# FPGA_bank15_16.net
KiCad netlist of a schematic drawn in Altium Designer
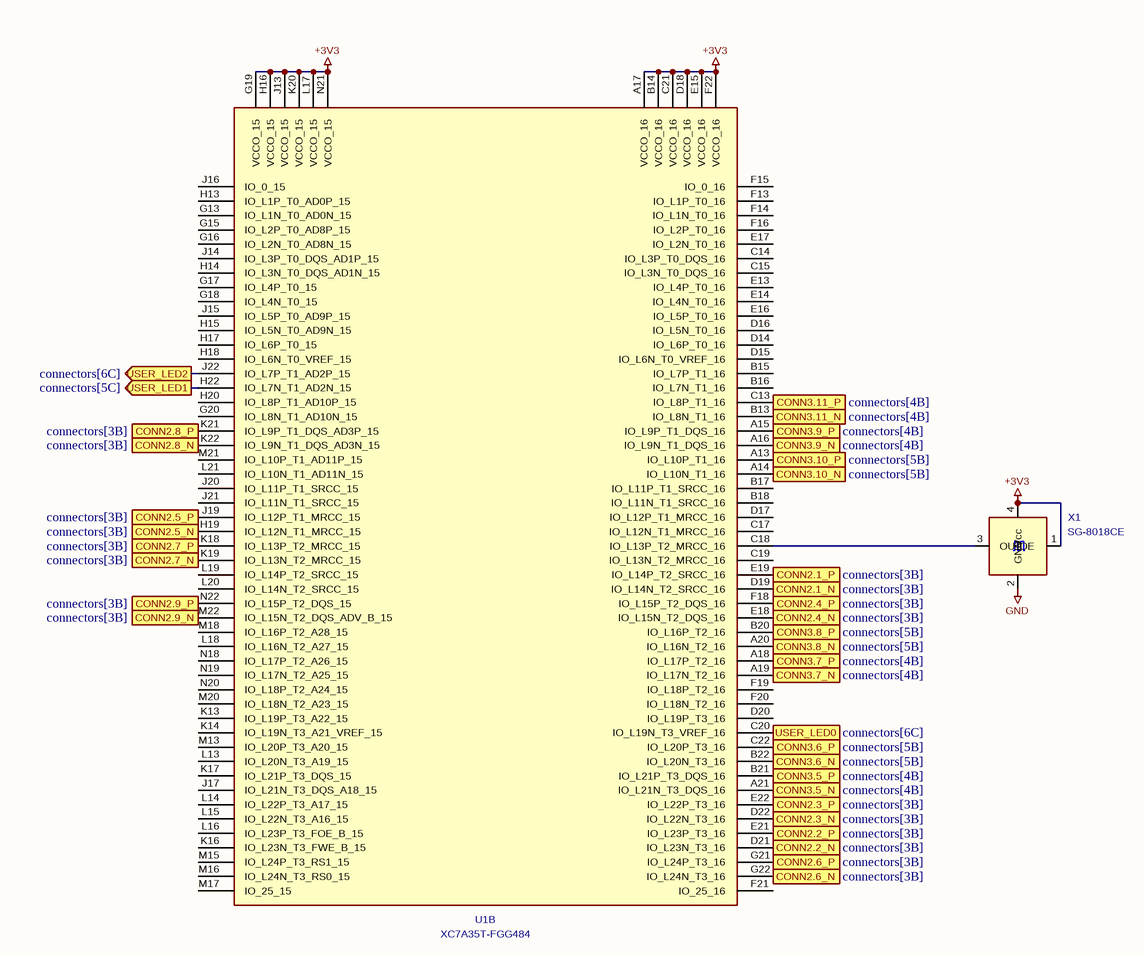
[diagram p0: FPGA_bank15_16.SchDoc]

(export (version "E")
  (design (tool "Eeschema 10.0.6"))
  (components
    (comp (ref "U1")
      (value "XC7A35T-FGG484")
      (footprint "FB-BGA-484_23.0x23.0mm_Layout22x22_P1.0mm")
      (libsource (lib "som_fpga") (part "XC7A35T-FGG484"))
    )
    (comp (ref "X1")
      (value "SG-8018CE")
      (footprint "Crystal_SMD_3225-4Pin_3.2x2.5mm")
      (libsource (lib "Oscillator") (part "SG-5032CCN"))
    )
  )
  (nets
    (net (code "1") (name "+3V3") (class "Default")
      (node (ref "U1") (pin "A17") (pinfunction "VCCO_16_A17") (pintype "passive"))
      (node (ref "U1") (pin "B14") (pinfunction "VCCO_16_B14") (pintype "passive"))
      (node (ref "U1") (pin "C21") (pinfunction "VCCO_16_C21") (pintype "passive"))
      (node (ref "U1") (pin "D18") (pinfunction "VCCO_16_D18") (pintype "passive"))
      (node (ref "U1") (pin "E15") (pinfunction "VCCO_16_E15") (pintype "passive"))
      (node (ref "U1") (pin "F22") (pinfunction "VCCO_16_F22") (pintype "passive"))
      (node (ref "U1") (pin "G19") (pinfunction "VCCO_15_G19") (pintype "passive"))
      (node (ref "U1") (pin "H16") (pinfunction "VCCO_15_H16") (pintype "passive"))
      (node (ref "U1") (pin "J13") (pinfunction "VCCO_15_J13") (pintype "passive"))
      (node (ref "U1") (pin "K20") (pinfunction "VCCO_15_K20") (pintype "passive"))
      (node (ref "U1") (pin "L17") (pinfunction "VCCO_15_L17") (pintype "passive"))
      (node (ref "U1") (pin "N21") (pinfunction "VCCO_15_N21") (pintype "passive"))
      (node (ref "X1") (pin "1") (pinfunction "OE_1") (pintype "passive"))
      (node (ref "X1") (pin "4") (pinfunction "Vcc_4") (pintype "passive"))
    )
    (net (code "2") (name "/CONN2.1_N") (class "Default")
      (node (ref "U1") (pin "D19") (pinfunction "IO_L14N_T2_SRCC_16_D19") (pintype "passive"))
    )
    (net (code "3") (name "/CONN2.1_P") (class "Default")
      (node (ref "U1") (pin "E19") (pinfunction "IO_L14P_T2_SRCC_16_E19") (pintype "passive"))
    )
    (net (code "4") (name "/CONN2.2_N") (class "Default")
      (node (ref "U1") (pin "D21") (pinfunction "IO_L23N_T3_16_D21") (pintype "passive"))
    )
    (net (code "5") (name "/CONN2.2_P") (class "Default")
      (node (ref "U1") (pin "E21") (pinfunction "IO_L23P_T3_16_E21") (pintype "passive"))
    )
    (net (code "6") (name "/CONN2.3_N") (class "Default")
      (node (ref "U1") (pin "D22") (pinfunction "IO_L22N_T3_16_D22") (pintype "passive"))
    )
    (net (code "7") (name "/CONN2.3_P") (class "Default")
      (node (ref "U1") (pin "E22") (pinfunction "IO_L22P_T3_16_E22") (pintype "passive"))
    )
    (net (code "8") (name "/CONN2.4_N") (class "Default")
      (node (ref "U1") (pin "E18") (pinfunction "IO_L15N_T2_DQS_16_E18") (pintype "passive"))
    )
    (net (code "9") (name "/CONN2.4_P") (class "Default")
      (node (ref "U1") (pin "F18") (pinfunction "IO_L15P_T2_DQS_16_F18") (pintype "passive"))
    )
    (net (code "10") (name "/CONN2.5_N") (class "Default")
      (node (ref "U1") (pin "H19") (pinfunction "IO_L12N_T1_MRCC_15_H19") (pintype "passive"))
    )
    (net (code "11") (name "/CONN2.5_P") (class "Default")
      (node (ref "U1") (pin "J19") (pinfunction "IO_L12P_T1_MRCC_15_J19") (pintype "passive"))
    )
    (net (code "12") (name "/CONN2.6_N") (class "Default")
      (node (ref "U1") (pin "G22") (pinfunction "IO_L24N_T3_16_G22") (pintype "passive"))
    )
    (net (code "13") (name "/CONN2.6_P") (class "Default")
      (node (ref "U1") (pin "G21") (pinfunction "IO_L24P_T3_16_G21") (pintype "passive"))
    )
    (net (code "14") (name "/CONN2.7_N") (class "Default")
      (node (ref "U1") (pin "K19") (pinfunction "IO_L13N_T2_MRCC_15_K19") (pintype "passive"))
    )
    (net (code "15") (name "/CONN2.7_P") (class "Default")
      (node (ref "U1") (pin "K18") (pinfunction "IO_L13P_T2_MRCC_15_K18") (pintype "passive"))
    )
    (net (code "16") (name "/CONN2.8_N") (class "Default")
      (node (ref "U1") (pin "K22") (pinfunction "IO_L9N_T1_DQS_AD3N_15_K22") (pintype "passive"))
    )
    (net (code "17") (name "/CONN2.8_P") (class "Default")
      (node (ref "U1") (pin "K21") (pinfunction "IO_L9P_T1_DQS_AD3P_15_K21") (pintype "passive"))
    )
    (net (code "18") (name "/CONN2.9_N") (class "Default")
      (node (ref "U1") (pin "M22") (pinfunction "IO_L15N_T2_DQS_ADV_B_15_M22") (pintype "passive"))
    )
    (net (code "19") (name "/CONN2.9_P") (class "Default")
      (node (ref "U1") (pin "N22") (pinfunction "IO_L15P_T2_DQS_15_N22") (pintype "passive"))
    )
    (net (code "20") (name "/CONN3.5_N") (class "Default")
      (node (ref "U1") (pin "A21") (pinfunction "IO_L21N_T3_DQS_16_A21") (pintype "passive"))
    )
    (net (code "21") (name "/CONN3.5_P") (class "Default")
      (node (ref "U1") (pin "B21") (pinfunction "IO_L21P_T3_DQS_16_B21") (pintype "passive"))
    )
    (net (code "22") (name "/CONN3.6_N") (class "Default")
      (node (ref "U1") (pin "B22") (pinfunction "IO_L20N_T3_16_B22") (pintype "passive"))
    )
    (net (code "23") (name "/CONN3.6_P") (class "Default")
      (node (ref "U1") (pin "C22") (pinfunction "IO_L20P_T3_16_C22") (pintype "passive"))
    )
    (net (code "24") (name "/CONN3.7_N") (class "Default")
      (node (ref "U1") (pin "A19") (pinfunction "IO_L17N_T2_16_A19") (pintype "passive"))
    )
    (net (code "25") (name "/CONN3.7_P") (class "Default")
      (node (ref "U1") (pin "A18") (pinfunction "IO_L17P_T2_16_A18") (pintype "passive"))
    )
    (net (code "26") (name "/CONN3.8_N") (class "Default")
      (node (ref "U1") (pin "A20") (pinfunction "IO_L16N_T2_16_A20") (pintype "passive"))
    )
    (net (code "27") (name "/CONN3.8_P") (class "Default")
      (node (ref "U1") (pin "B20") (pinfunction "IO_L16P_T2_16_B20") (pintype "passive"))
    )
    (net (code "28") (name "/CONN3.9_N") (class "Default")
      (node (ref "U1") (pin "A16") (pinfunction "IO_L9N_T1_DQS_16_A16") (pintype "passive"))
    )
    (net (code "29") (name "/CONN3.9_P") (class "Default")
      (node (ref "U1") (pin "A15") (pinfunction "IO_L9P_T1_DQS_16_A15") (pintype "passive"))
    )
    (net (code "30") (name "/CONN3.10_N") (class "Default")
      (node (ref "U1") (pin "A14") (pinfunction "IO_L10N_T1_16_A14") (pintype "passive"))
    )
    (net (code "31") (name "/CONN3.10_P") (class "Default")
      (node (ref "U1") (pin "A13") (pinfunction "IO_L10P_T1_16_A13") (pintype "passive"))
    )
    (net (code "32") (name "/CONN3.11_N") (class "Default")
      (node (ref "U1") (pin "B13") (pinfunction "IO_L8N_T1_16_B13") (pintype "passive"))
    )
    (net (code "33") (name "/CONN3.11_P") (class "Default")
      (node (ref "U1") (pin "C13") (pinfunction "IO_L8P_T1_16_C13") (pintype "passive"))
    )
    (net (code "34") (name "/USER_LED0") (class "Default")
      (node (ref "U1") (pin "C20") (pinfunction "IO_L19N_T3_VREF_16_C20") (pintype "passive"))
    )
    (net (code "35") (name "/USER_LED1") (class "Default")
      (node (ref "U1") (pin "H22") (pinfunction "IO_L7N_T1_AD2N_15_H22") (pintype "passive"))
    )
    (net (code "36") (name "/USER_LED2") (class "Default")
      (node (ref "U1") (pin "J22") (pinfunction "IO_L7P_T1_AD2P_15_J22") (pintype "passive"))
    )
    (net (code "37") (name "GND") (class "Default")
      (node (ref "X1") (pin "2") (pinfunction "GND_2") (pintype "passive"))
    )
    (net (code "38") (name "Net-(U1B-IO_L13P_T2_MRCC_16)") (class "Default")
      (node (ref "U1") (pin "C18") (pinfunction "IO_L13P_T2_MRCC_16_C18") (pintype "passive"))
      (node (ref "X1") (pin "3") (pinfunction "OUT_3") (pintype "passive"))
    )
    (net (code "39") (name "unconnected-(U1B-IO_0_15-PadJ16)") (class "Default")
      (node (ref "U1") (pin "J16") (pinfunction "IO_0_15_J16") (pintype "passive"))
    )
    (net (code "40") (name "unconnected-(U1B-IO_0_16-PadF15)") (class "Default")
      (node (ref "U1") (pin "F15") (pinfunction "IO_0_16_F15") (pintype "passive"))
    )
    (net (code "41") (name "unconnected-(U1B-IO_25_15-PadM17)") (class "Default")
      (node (ref "U1") (pin "M17") (pinfunction "IO_25_15_M17") (pintype "passive"))
    )
    (net (code "42") (name "unconnected-(U1B-IO_25_16-PadF21)") (class "Default")
      (node (ref "U1") (pin "F21") (pinfunction "IO_25_16_F21") (pintype "passive"))
    )
    (net (code "43") (name "unconnected-(U1B-IO_L1N_T0_16-PadF14)") (class "Default")
      (node (ref "U1") (pin "F14") (pinfunction "IO_L1N_T0_16_F14") (pintype "passive"))
    )
    (net (code "44") (name "unconnected-(U1B-IO_L1N_T0_AD0N_15-PadG13)") (class "Default")
      (node (ref "U1") (pin "G13") (pinfunction "IO_L1N_T0_AD0N_15_G13") (pintype "passive"))
    )
    (net (code "45") (name "unconnected-(U1B-IO_L1P_T0_16-PadF13)") (class "Default")
      (node (ref "U1") (pin "F13") (pinfunction "IO_L1P_T0_16_F13") (pintype "passive"))
    )
    (net (code "46") (name "unconnected-(U1B-IO_L1P_T0_AD0P_15-PadH13)") (class "Default")
      (node (ref "U1") (pin "H13") (pinfunction "IO_L1P_T0_AD0P_15_H13") (pintype "passive"))
    )
    (net (code "47") (name "unconnected-(U1B-IO_L2N_T0_16-PadE17)") (class "Default")
      (node (ref "U1") (pin "E17") (pinfunction "IO_L2N_T0_16_E17") (pintype "passive"))
    )
    (net (code "48") (name "unconnected-(U1B-IO_L2N_T0_AD8N_15-PadG16)") (class "Default")
      (node (ref "U1") (pin "G16") (pinfunction "IO_L2N_T0_AD8N_15_G16") (pintype "passive"))
    )
    (net (code "49") (name "unconnected-(U1B-IO_L2P_T0_16-PadF16)") (class "Default")
      (node (ref "U1") (pin "F16") (pinfunction "IO_L2P_T0_16_F16") (pintype "passive"))
    )
    (net (code "50") (name "unconnected-(U1B-IO_L2P_T0_AD8P_15-PadG15)") (class "Default")
      (node (ref "U1") (pin "G15") (pinfunction "IO_L2P_T0_AD8P_15_G15") (pintype "passive"))
    )
    (net (code "51") (name "unconnected-(U1B-IO_L3N_T0_DQS_16-PadC15)") (class "Default")
      (node (ref "U1") (pin "C15") (pinfunction "IO_L3N_T0_DQS_16_C15") (pintype "passive"))
    )
    (net (code "52") (name "unconnected-(U1B-IO_L3N_T0_DQS_AD1N_15-PadH14)") (class "Default")
      (node (ref "U1") (pin "H14") (pinfunction "IO_L3N_T0_DQS_AD1N_15_H14") (pintype "passive"))
    )
    (net (code "53") (name "unconnected-(U1B-IO_L3P_T0_DQS_16-PadC14)") (class "Default")
      (node (ref "U1") (pin "C14") (pinfunction "IO_L3P_T0_DQS_16_C14") (pintype "passive"))
    )
    (net (code "54") (name "unconnected-(U1B-IO_L3P_T0_DQS_AD1P_15-PadJ14)") (class "Default")
      (node (ref "U1") (pin "J14") (pinfunction "IO_L3P_T0_DQS_AD1P_15_J14") (pintype "passive"))
    )
    (net (code "55") (name "unconnected-(U1B-IO_L4N_T0_15-PadG18)") (class "Default")
      (node (ref "U1") (pin "G18") (pinfunction "IO_L4N_T0_15_G18") (pintype "passive"))
    )
    (net (code "56") (name "unconnected-(U1B-IO_L4N_T0_16-PadE14)") (class "Default")
      (node (ref "U1") (pin "E14") (pinfunction "IO_L4N_T0_16_E14") (pintype "passive"))
    )
    (net (code "57") (name "unconnected-(U1B-IO_L4P_T0_15-PadG17)") (class "Default")
      (node (ref "U1") (pin "G17") (pinfunction "IO_L4P_T0_15_G17") (pintype "passive"))
    )
    (net (code "58") (name "unconnected-(U1B-IO_L4P_T0_16-PadE13)") (class "Default")
      (node (ref "U1") (pin "E13") (pinfunction "IO_L4P_T0_16_E13") (pintype "passive"))
    )
    (net (code "59") (name "unconnected-(U1B-IO_L5N_T0_16-PadD16)") (class "Default")
      (node (ref "U1") (pin "D16") (pinfunction "IO_L5N_T0_16_D16") (pintype "passive"))
    )
    (net (code "60") (name "unconnected-(U1B-IO_L5N_T0_AD9N_15-PadH15)") (class "Default")
      (node (ref "U1") (pin "H15") (pinfunction "IO_L5N_T0_AD9N_15_H15") (pintype "passive"))
    )
    (net (code "61") (name "unconnected-(U1B-IO_L5P_T0_16-PadE16)") (class "Default")
      (node (ref "U1") (pin "E16") (pinfunction "IO_L5P_T0_16_E16") (pintype "passive"))
    )
    (net (code "62") (name "unconnected-(U1B-IO_L5P_T0_AD9P_15-PadJ15)") (class "Default")
      (node (ref "U1") (pin "J15") (pinfunction "IO_L5P_T0_AD9P_15_J15") (pintype "passive"))
    )
    (net (code "63") (name "unconnected-(U1B-IO_L6N_T0_VREF_15-PadH18)") (class "Default")
      (node (ref "U1") (pin "H18") (pinfunction "IO_L6N_T0_VREF_15_H18") (pintype "passive"))
    )
    (net (code "64") (name "unconnected-(U1B-IO_L6N_T0_VREF_16-PadD15)") (class "Default")
      (node (ref "U1") (pin "D15") (pinfunction "IO_L6N_T0_VREF_16_D15") (pintype "passive"))
    )
    (net (code "65") (name "unconnected-(U1B-IO_L6P_T0_15-PadH17)") (class "Default")
      (node (ref "U1") (pin "H17") (pinfunction "IO_L6P_T0_15_H17") (pintype "passive"))
    )
    (net (code "66") (name "unconnected-(U1B-IO_L6P_T0_16-PadD14)") (class "Default")
      (node (ref "U1") (pin "D14") (pinfunction "IO_L6P_T0_16_D14") (pintype "passive"))
    )
    (net (code "67") (name "unconnected-(U1B-IO_L7N_T1_16-PadB16)") (class "Default")
      (node (ref "U1") (pin "B16") (pinfunction "IO_L7N_T1_16_B16") (pintype "passive"))
    )
    (net (code "68") (name "unconnected-(U1B-IO_L7P_T1_16-PadB15)") (class "Default")
      (node (ref "U1") (pin "B15") (pinfunction "IO_L7P_T1_16_B15") (pintype "passive"))
    )
    (net (code "69") (name "unconnected-(U1B-IO_L8N_T1_AD10N_15-PadG20)") (class "Default")
      (node (ref "U1") (pin "G20") (pinfunction "IO_L8N_T1_AD10N_15_G20") (pintype "passive"))
    )
    (net (code "70") (name "unconnected-(U1B-IO_L8P_T1_AD10P_15-PadH20)") (class "Default")
      (node (ref "U1") (pin "H20") (pinfunction "IO_L8P_T1_AD10P_15_H20") (pintype "passive"))
    )
    (net (code "71") (name "unconnected-(U1B-IO_L10N_T1_AD11N_15-PadL21)") (class "Default")
      (node (ref "U1") (pin "L21") (pinfunction "IO_L10N_T1_AD11N_15_L21") (pintype "passive"))
    )
    (net (code "72") (name "unconnected-(U1B-IO_L10P_T1_AD11P_15-PadM21)") (class "Default")
      (node (ref "U1") (pin "M21") (pinfunction "IO_L10P_T1_AD11P_15_M21") (pintype "passive"))
    )
    (net (code "73") (name "unconnected-(U1B-IO_L11N_T1_SRCC_15-PadJ21)") (class "Default")
      (node (ref "U1") (pin "J21") (pinfunction "IO_L11N_T1_SRCC_15_J21") (pintype "passive"))
    )
    (net (code "74") (name "unconnected-(U1B-IO_L11N_T1_SRCC_16-PadB18)") (class "Default")
      (node (ref "U1") (pin "B18") (pinfunction "IO_L11N_T1_SRCC_16_B18") (pintype "passive"))
    )
    (net (code "75") (name "unconnected-(U1B-IO_L11P_T1_SRCC_15-PadJ20)") (class "Default")
      (node (ref "U1") (pin "J20") (pinfunction "IO_L11P_T1_SRCC_15_J20") (pintype "passive"))
    )
    (net (code "76") (name "unconnected-(U1B-IO_L11P_T1_SRCC_16-PadB17)") (class "Default")
      (node (ref "U1") (pin "B17") (pinfunction "IO_L11P_T1_SRCC_16_B17") (pintype "passive"))
    )
    (net (code "77") (name "unconnected-(U1B-IO_L12N_T1_MRCC_16-PadC17)") (class "Default")
      (node (ref "U1") (pin "C17") (pinfunction "IO_L12N_T1_MRCC_16_C17") (pintype "passive"))
    )
    (net (code "78") (name "unconnected-(U1B-IO_L12P_T1_MRCC_16-PadD17)") (class "Default")
      (node (ref "U1") (pin "D17") (pinfunction "IO_L12P_T1_MRCC_16_D17") (pintype "passive"))
    )
    (net (code "79") (name "unconnected-(U1B-IO_L13N_T2_MRCC_16-PadC19)") (class "Default")
      (node (ref "U1") (pin "C19") (pinfunction "IO_L13N_T2_MRCC_16_C19") (pintype "passive"))
    )
    (net (code "80") (name "unconnected-(U1B-IO_L14N_T2_SRCC_15-PadL20)") (class "Default")
      (node (ref "U1") (pin "L20") (pinfunction "IO_L14N_T2_SRCC_15_L20") (pintype "passive"))
    )
    (net (code "81") (name "unconnected-(U1B-IO_L14P_T2_SRCC_15-PadL19)") (class "Default")
      (node (ref "U1") (pin "L19") (pinfunction "IO_L14P_T2_SRCC_15_L19") (pintype "passive"))
    )
    (net (code "82") (name "unconnected-(U1B-IO_L16N_T2_A27_15-PadL18)") (class "Default")
      (node (ref "U1") (pin "L18") (pinfunction "IO_L16N_T2_A27_15_L18") (pintype "passive"))
    )
    (net (code "83") (name "unconnected-(U1B-IO_L16P_T2_A28_15-PadM18)") (class "Default")
      (node (ref "U1") (pin "M18") (pinfunction "IO_L16P_T2_A28_15_M18") (pintype "passive"))
    )
    (net (code "84") (name "unconnected-(U1B-IO_L17N_T2_A25_15-PadN19)") (class "Default")
      (node (ref "U1") (pin "N19") (pinfunction "IO_L17N_T2_A25_15_N19") (pintype "passive"))
    )
    (net (code "85") (name "unconnected-(U1B-IO_L17P_T2_A26_15-PadN18)") (class "Default")
      (node (ref "U1") (pin "N18") (pinfunction "IO_L17P_T2_A26_15_N18") (pintype "passive"))
    )
    (net (code "86") (name "unconnected-(U1B-IO_L18N_T2_16-PadF20)") (class "Default")
      (node (ref "U1") (pin "F20") (pinfunction "IO_L18N_T2_16_F20") (pintype "passive"))
    )
    (net (code "87") (name "unconnected-(U1B-IO_L18N_T2_A23_15-PadM20)") (class "Default")
      (node (ref "U1") (pin "M20") (pinfunction "IO_L18N_T2_A23_15_M20") (pintype "passive"))
    )
    (net (code "88") (name "unconnected-(U1B-IO_L18P_T2_16-PadF19)") (class "Default")
      (node (ref "U1") (pin "F19") (pinfunction "IO_L18P_T2_16_F19") (pintype "passive"))
    )
    (net (code "89") (name "unconnected-(U1B-IO_L18P_T2_A24_15-PadN20)") (class "Default")
      (node (ref "U1") (pin "N20") (pinfunction "IO_L18P_T2_A24_15_N20") (pintype "passive"))
    )
    (net (code "90") (name "unconnected-(U1B-IO_L19N_T3_A21_VREF_15-PadK14)") (class "Default")
      (node (ref "U1") (pin "K14") (pinfunction "IO_L19N_T3_A21_VREF_15_K14") (pintype "passive"))
    )
    (net (code "91") (name "unconnected-(U1B-IO_L19P_T3_16-PadD20)") (class "Default")
      (node (ref "U1") (pin "D20") (pinfunction "IO_L19P_T3_16_D20") (pintype "passive"))
    )
    (net (code "92") (name "unconnected-(U1B-IO_L19P_T3_A22_15-PadK13)") (class "Default")
      (node (ref "U1") (pin "K13") (pinfunction "IO_L19P_T3_A22_15_K13") (pintype "passive"))
    )
    (net (code "93") (name "unconnected-(U1B-IO_L20N_T3_A19_15-PadL13)") (class "Default")
      (node (ref "U1") (pin "L13") (pinfunction "IO_L20N_T3_A19_15_L13") (pintype "passive"))
    )
    (net (code "94") (name "unconnected-(U1B-IO_L20P_T3_A20_15-PadM13)") (class "Default")
      (node (ref "U1") (pin "M13") (pinfunction "IO_L20P_T3_A20_15_M13") (pintype "passive"))
    )
    (net (code "95") (name "unconnected-(U1B-IO_L21N_T3_DQS_A18_15-PadJ17)") (class "Default")
      (node (ref "U1") (pin "J17") (pinfunction "IO_L21N_T3_DQS_A18_15_J17") (pintype "passive"))
    )
    (net (code "96") (name "unconnected-(U1B-IO_L21P_T3_DQS_15-PadK17)") (class "Default")
      (node (ref "U1") (pin "K17") (pinfunction "IO_L21P_T3_DQS_15_K17") (pintype "passive"))
    )
    (net (code "97") (name "unconnected-(U1B-IO_L22N_T3_A16_15-PadL15)") (class "Default")
      (node (ref "U1") (pin "L15") (pinfunction "IO_L22N_T3_A16_15_L15") (pintype "passive"))
    )
    (net (code "98") (name "unconnected-(U1B-IO_L22P_T3_A17_15-PadL14)") (class "Default")
      (node (ref "U1") (pin "L14") (pinfunction "IO_L22P_T3_A17_15_L14") (pintype "passive"))
    )
    (net (code "99") (name "unconnected-(U1B-IO_L23N_T3_FWE_B_15-PadK16)") (class "Default")
      (node (ref "U1") (pin "K16") (pinfunction "IO_L23N_T3_FWE_B_15_K16") (pintype "passive"))
    )
    (net (code "100") (name "unconnected-(U1B-IO_L23P_T3_FOE_B_15-PadL16)") (class "Default")
      (node (ref "U1") (pin "L16") (pinfunction "IO_L23P_T3_FOE_B_15_L16") (pintype "passive"))
    )
    (net (code "101") (name "unconnected-(U1B-IO_L24N_T3_RS0_15-PadM16)") (class "Default")
      (node (ref "U1") (pin "M16") (pinfunction "IO_L24N_T3_RS0_15_M16") (pintype "passive"))
    )
    (net (code "102") (name "unconnected-(U1B-IO_L24P_T3_RS1_15-PadM15)") (class "Default")
      (node (ref "U1") (pin "M15") (pinfunction "IO_L24P_T3_RS1_15_M15") (pintype "passive"))
    )
  )
)
